# SRV-1_Expansion_Board.net
KiCad netlist of a schematic drawn in EAGLE
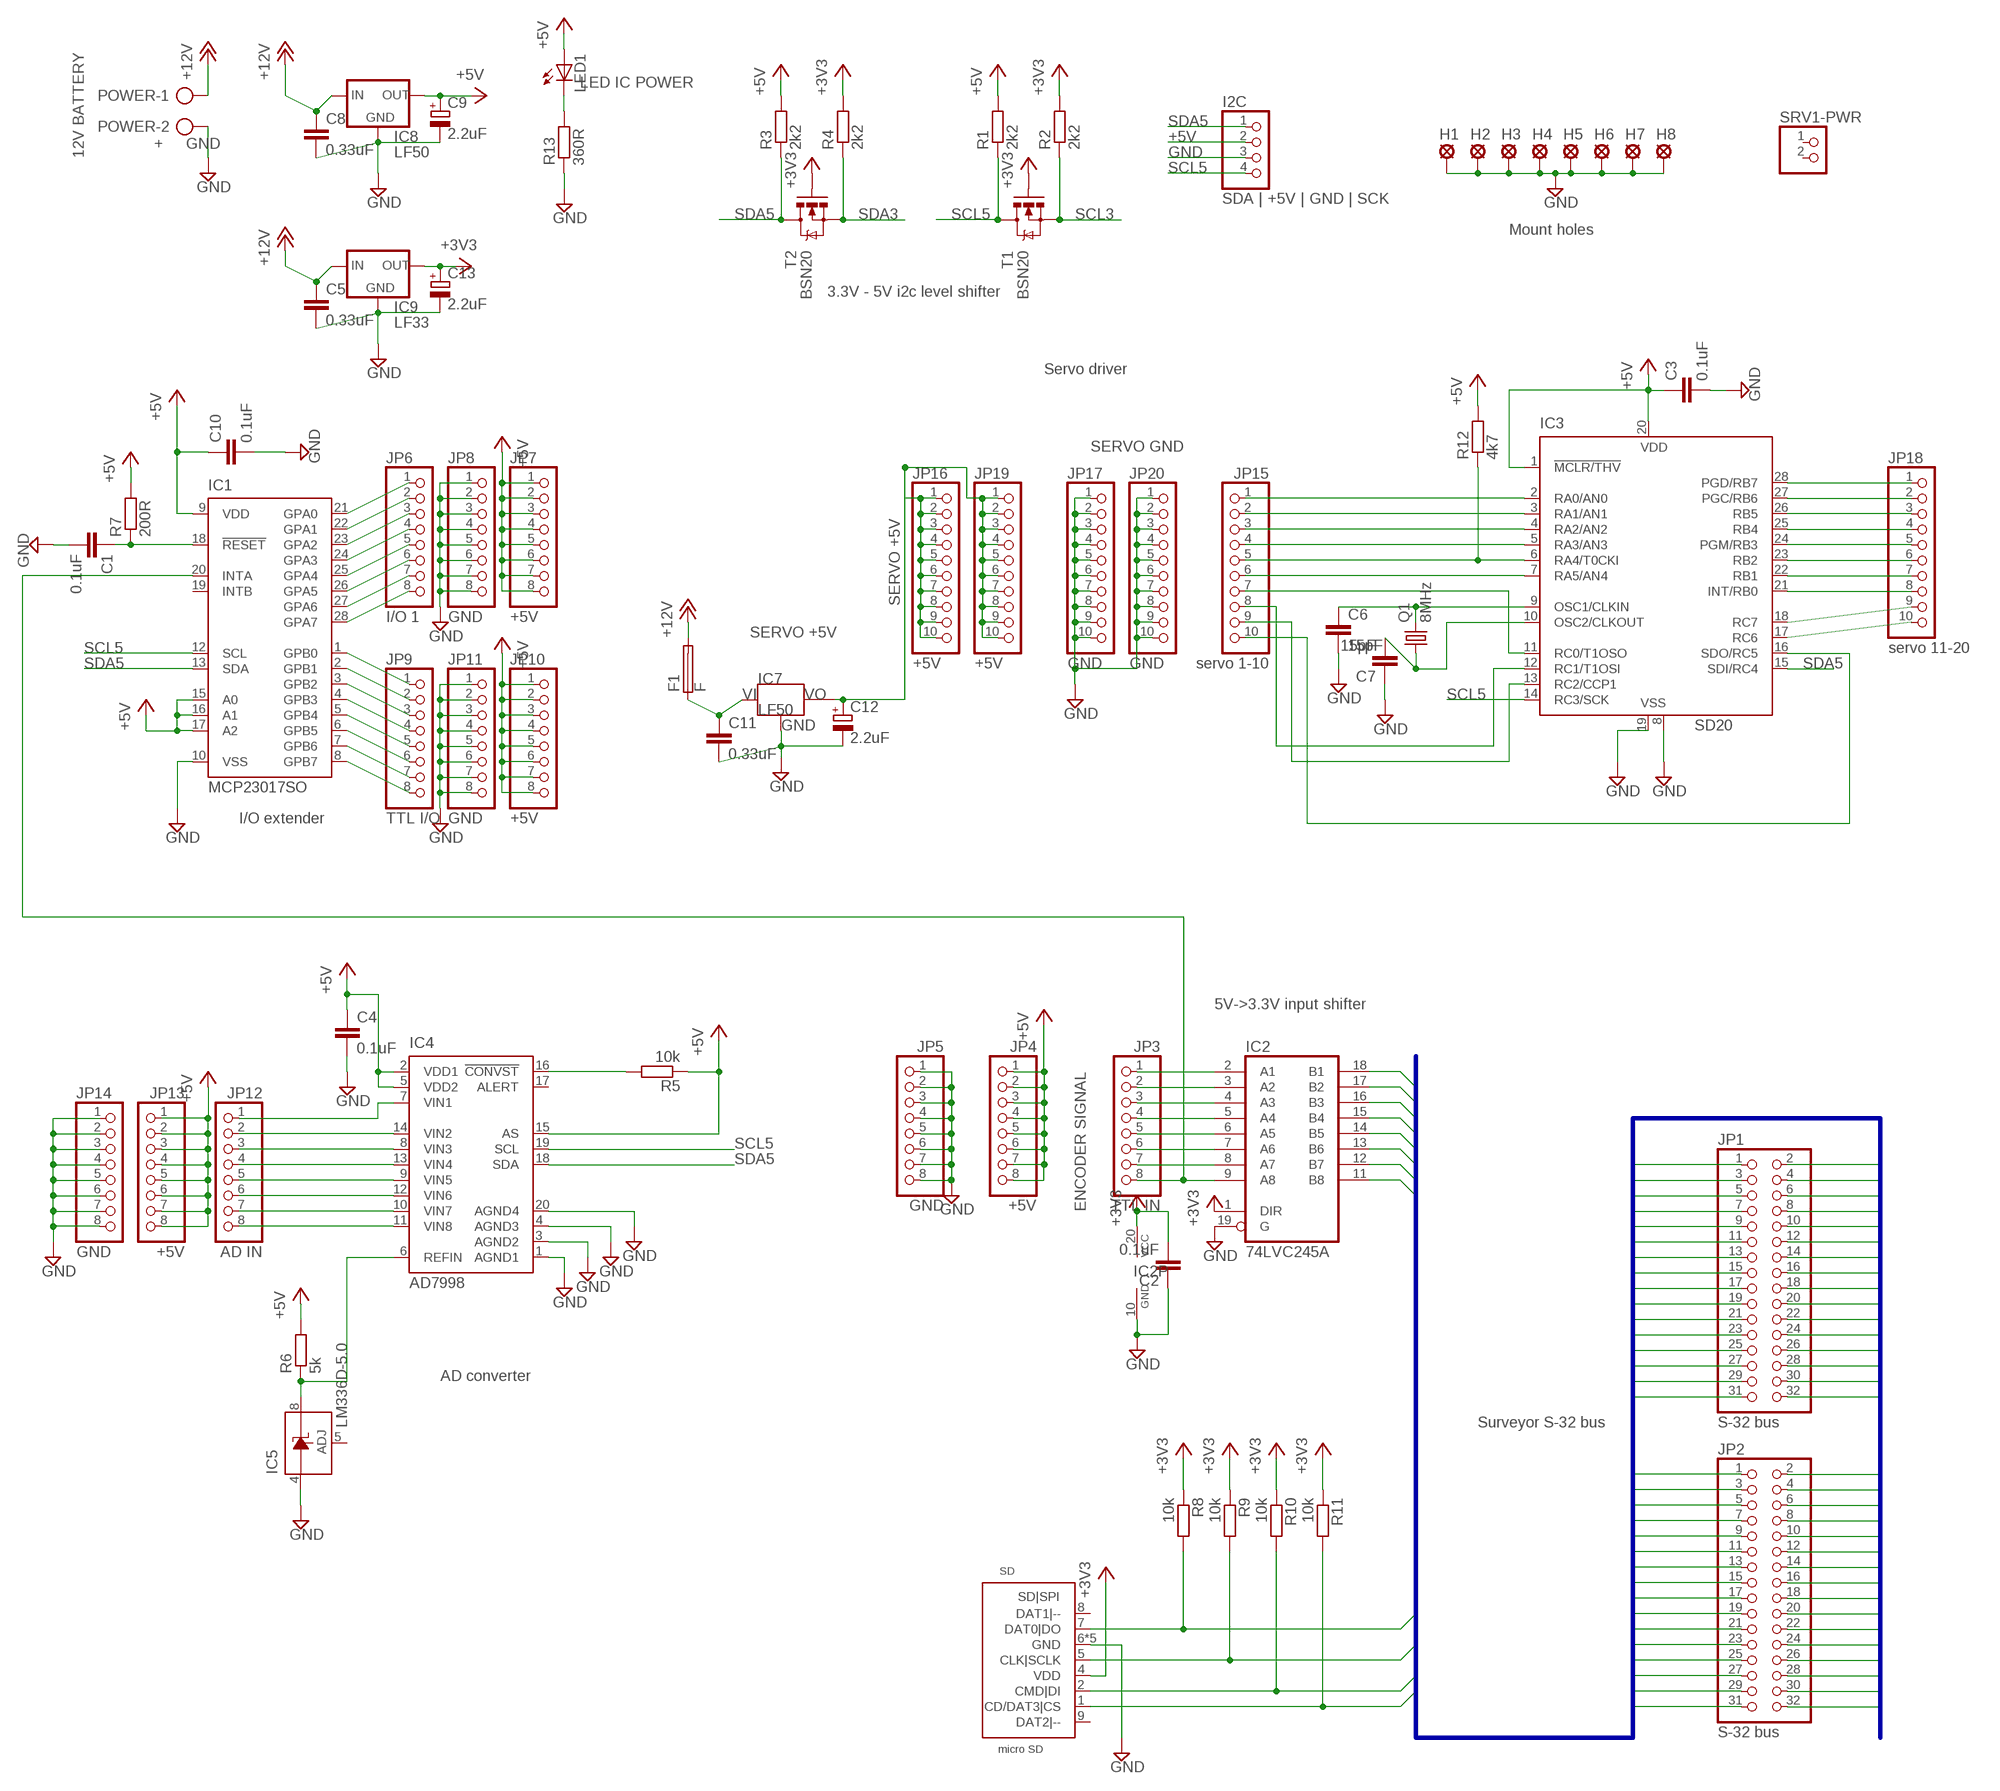
[diagram p0: schematic, sheet 1]

(export (version "E")
  (design (tool "Eeschema 10.0.6"))
  (components
    (comp (ref "C1")
      (value "0.1uF")
      (footprint "eagle-import:1206")
      (libsource (lib "eagle-import") (part "CAP1206"))
    )
    (comp (ref "C2")
      (value "0.1uF")
      (footprint "eagle-import:1206")
      (libsource (lib "eagle-import") (part "CAP1206"))
    )
    (comp (ref "C3")
      (value "0.1uF")
      (footprint "eagle-import:1206")
      (libsource (lib "eagle-import") (part "CAP1206"))
    )
    (comp (ref "C4")
      (value "0.1uF")
      (footprint "eagle-import:1206")
      (libsource (lib "eagle-import") (part "CAP1206"))
    )
    (comp (ref "C5")
      (value "0.33uF")
      (footprint "eagle-import:C025-024X044")
      (libsource (lib "eagle-import") (part "C-EU025-024X044"))
    )
    (comp (ref "C6")
      (value "15pF")
      (footprint "eagle-import:1206")
      (libsource (lib "eagle-import") (part "CAP1206"))
    )
    (comp (ref "C7")
      (value "15pF")
      (footprint "eagle-import:1206")
      (libsource (lib "eagle-import") (part "CAP1206"))
    )
    (comp (ref "C8")
      (value "0.33uF")
      (footprint "eagle-import:C025-024X044")
      (libsource (lib "eagle-import") (part "C-EU025-024X044"))
    )
    (comp (ref "C9")
      (value "2.2uF")
      (footprint "eagle-import:E1,8-4")
      (libsource (lib "eagle-import") (part "CPOL-EUE1.8-4"))
    )
    (comp (ref "C10")
      (value "0.1uF")
      (footprint "eagle-import:1206")
      (libsource (lib "eagle-import") (part "CAP1206"))
    )
    (comp (ref "C11")
      (value "0.33uF")
      (footprint "eagle-import:C025-024X044")
      (libsource (lib "eagle-import") (part "C-EU025-024X044"))
    )
    (comp (ref "C12")
      (value "2.2uF")
      (footprint "eagle-import:E1,8-4")
      (libsource (lib "eagle-import") (part "CPOL-EUE1.8-4"))
    )
    (comp (ref "C13")
      (value "2.2uF")
      (footprint "eagle-import:E1,8-4")
      (libsource (lib "eagle-import") (part "CPOL-EUE1.8-4"))
    )
    (comp (ref "F1") (value "F") (footprint "eagle-import:TE5") (libsource (lib "eagle-import") (part "TE5")))
    (comp (ref "H1")
      (value "LSP35")
      (footprint "eagle-import:LSP35")
      (libsource (lib "eagle-import") (part "LSP35"))
    )
    (comp (ref "H2")
      (value "LSP35")
      (footprint "eagle-import:LSP35")
      (libsource (lib "eagle-import") (part "LSP35"))
    )
    (comp (ref "H3")
      (value "LSP35")
      (footprint "eagle-import:LSP35")
      (libsource (lib "eagle-import") (part "LSP35"))
    )
    (comp (ref "H4")
      (value "LSP35")
      (footprint "eagle-import:LSP35")
      (libsource (lib "eagle-import") (part "LSP35"))
    )
    (comp (ref "H5")
      (value "LSP40")
      (footprint "eagle-import:LSP40")
      (libsource (lib "eagle-import") (part "LSP40"))
    )
    (comp (ref "H6")
      (value "LSP40")
      (footprint "eagle-import:LSP40")
      (libsource (lib "eagle-import") (part "LSP40"))
    )
    (comp (ref "H7")
      (value "LSP40")
      (footprint "eagle-import:LSP40")
      (libsource (lib "eagle-import") (part "LSP40"))
    )
    (comp (ref "H8")
      (value "LSP40")
      (footprint "eagle-import:LSP40")
      (libsource (lib "eagle-import") (part "LSP40"))
    )
    (comp (ref "I2C")
      (value "SDA | +5V | GND | SCK")
      (footprint "eagle-import:1X04")
      (libsource (lib "eagle-import") (part "PINHD-1X4"))
    )
    (comp (ref "IC1")
      (value "MCP23017SO")
      (footprint "eagle-import:SO28W")
      (fields (field (name "MF") "MICROCHIP") (field (name "MPN") "MCP23017-E/SO"))
      (libsource (lib "eagle-import") (part "MCP23017SO"))
    )
    (comp (ref "IC2")
      (value "74LVC245A")
      (footprint "eagle-import:SO20W")
      (libsource (lib "eagle-import") (part "74245DWLS"))
    )
    (comp (ref "IC3")
      (value "SD20")
      (footprint "eagle-import:DIL28-3")
      (fields (field (name "MF") "MICROCHIP") (field (name "MPN") "PIC16F872-I/SP"))
      (libsource (lib "eagle-import") (part "PIC16872PF"))
    )
    (comp (ref "IC4")
      (value "AD7998")
      (footprint "eagle-import:TSSOP20")
      (libsource (lib "eagle-import") (part "AD7998"))
    )
    (comp (ref "IC5")
      (value "LM336D-5.0")
      (footprint "eagle-import:SO08")
      (libsource (lib "eagle-import") (part "LM336D"))
    )
    (comp (ref "IC7")
      (value "LF50")
      (footprint "eagle-import:TO220V")
      (libsource (lib "eagle-import") (part "L7805"))
    )
    (comp (ref "IC8")
      (value "LF50")
      (footprint "eagle-import:DPAK")
      (libsource (lib "eagle-import") (part "78XXCDT"))
    )
    (comp (ref "IC9")
      (value "LF33")
      (footprint "eagle-import:DPAK")
      (libsource (lib "eagle-import") (part "78XXCDT"))
    )
    (comp (ref "JP1")
      (value "S-32 bus")
      (footprint "eagle-import:2X16")
      (libsource (lib "eagle-import") (part "PINHD-2X16"))
    )
    (comp (ref "JP2")
      (value "S-32 bus")
      (footprint "eagle-import:2X16")
      (libsource (lib "eagle-import") (part "PINHD-2X16"))
    )
    (comp (ref "JP3")
      (value "TTL IN")
      (footprint "eagle-import:1X08")
      (libsource (lib "eagle-import") (part "PINHD-1X8"))
    )
    (comp (ref "JP4")
      (value "+5V")
      (footprint "eagle-import:1X08")
      (libsource (lib "eagle-import") (part "PINHD-1X8"))
    )
    (comp (ref "JP5")
      (value "GND")
      (footprint "eagle-import:1X08")
      (libsource (lib "eagle-import") (part "PINHD-1X8"))
    )
    (comp (ref "JP6")
      (value "I/O 1")
      (footprint "eagle-import:1X08")
      (libsource (lib "eagle-import") (part "PINHD-1X8"))
    )
    (comp (ref "JP7")
      (value "+5V")
      (footprint "eagle-import:1X08")
      (libsource (lib "eagle-import") (part "PINHD-1X8"))
    )
    (comp (ref "JP8")
      (value "GND")
      (footprint "eagle-import:1X08")
      (libsource (lib "eagle-import") (part "PINHD-1X8"))
    )
    (comp (ref "JP9")
      (value "TTL I/O")
      (footprint "eagle-import:1X08")
      (libsource (lib "eagle-import") (part "PINHD-1X8"))
    )
    (comp (ref "JP10")
      (value "+5V")
      (footprint "eagle-import:1X08")
      (libsource (lib "eagle-import") (part "PINHD-1X8"))
    )
    (comp (ref "JP11")
      (value "GND")
      (footprint "eagle-import:1X08")
      (libsource (lib "eagle-import") (part "PINHD-1X8"))
    )
    (comp (ref "JP12")
      (value "AD IN")
      (footprint "eagle-import:1X08")
      (libsource (lib "eagle-import") (part "PINHD-1X8"))
    )
    (comp (ref "JP13")
      (value "+5V")
      (footprint "eagle-import:1X08")
      (libsource (lib "eagle-import") (part "PINHD-1X8"))
    )
    (comp (ref "JP14")
      (value "GND")
      (footprint "eagle-import:1X08")
      (libsource (lib "eagle-import") (part "PINHD-1X8"))
    )
    (comp (ref "JP15")
      (value "servo 1-10")
      (footprint "eagle-import:1X10")
      (libsource (lib "eagle-import") (part "PINHD-1X10"))
    )
    (comp (ref "JP16")
      (value "+5V")
      (footprint "eagle-import:1X10")
      (libsource (lib "eagle-import") (part "PINHD-1X10"))
    )
    (comp (ref "JP17")
      (value "GND")
      (footprint "eagle-import:1X10")
      (libsource (lib "eagle-import") (part "PINHD-1X10"))
    )
    (comp (ref "JP18")
      (value "servo 11-20")
      (footprint "eagle-import:1X10")
      (libsource (lib "eagle-import") (part "PINHD-1X10"))
    )
    (comp (ref "JP19")
      (value "+5V")
      (footprint "eagle-import:1X10")
      (libsource (lib "eagle-import") (part "PINHD-1X10"))
    )
    (comp (ref "JP20")
      (value "GND")
      (footprint "eagle-import:1X10")
      (libsource (lib "eagle-import") (part "PINHD-1X10"))
    )
    (comp (ref "LED1")
      (value "LEDCHIPLED_1206")
      (footprint "eagle-import:CHIPLED_1206")
      (libsource (lib "eagle-import") (part "LEDCHIPLED_1206"))
    )
    (comp (ref "POWER")
      (value "+ GND")
      (footprint "eagle-import:AK500_2")
      (libsource (lib "eagle-import") (part "AK500/2"))
    )
    (comp (ref "Q1")
      (value "8MHz")
      (footprint "eagle-import:HC49U70")
      (libsource (lib "eagle-import") (part "CRYSTALHC49U70"))
    )
    (comp (ref "R1")
      (value "2k2")
      (footprint "eagle-import:R1206")
      (libsource (lib "eagle-import") (part "R-EU_R1206"))
    )
    (comp (ref "R2")
      (value "2k2")
      (footprint "eagle-import:R1206")
      (libsource (lib "eagle-import") (part "R-EU_R1206"))
    )
    (comp (ref "R3")
      (value "2k2")
      (footprint "eagle-import:R1206")
      (libsource (lib "eagle-import") (part "R-EU_R1206"))
    )
    (comp (ref "R4")
      (value "2k2")
      (footprint "eagle-import:R1206")
      (libsource (lib "eagle-import") (part "R-EU_R1206"))
    )
    (comp (ref "R5")
      (value "10k")
      (footprint "eagle-import:R1206")
      (libsource (lib "eagle-import") (part "R-EU_R1206"))
    )
    (comp (ref "R6")
      (value "5k")
      (footprint "eagle-import:R1206")
      (libsource (lib "eagle-import") (part "R-EU_R1206"))
    )
    (comp (ref "R7")
      (value "200R")
      (footprint "eagle-import:R1206")
      (libsource (lib "eagle-import") (part "R-EU_R1206"))
    )
    (comp (ref "R8")
      (value "10k")
      (footprint "eagle-import:R1206")
      (libsource (lib "eagle-import") (part "R-EU_R1206"))
    )
    (comp (ref "R9")
      (value "10k")
      (footprint "eagle-import:R1206")
      (libsource (lib "eagle-import") (part "R-EU_R1206"))
    )
    (comp (ref "R10")
      (value "10k")
      (footprint "eagle-import:R1206")
      (libsource (lib "eagle-import") (part "R-EU_R1206"))
    )
    (comp (ref "R11")
      (value "10k")
      (footprint "eagle-import:R1206")
      (libsource (lib "eagle-import") (part "R-EU_R1206"))
    )
    (comp (ref "R12")
      (value "4k7")
      (footprint "eagle-import:R1206")
      (libsource (lib "eagle-import") (part "R-EU_R1206"))
    )
    (comp (ref "R13")
      (value "360R")
      (footprint "eagle-import:R1206")
      (libsource (lib "eagle-import") (part "R-EU_R1206"))
    )
    (comp (ref "SD")
      (value "micro SD")
      (footprint "eagle-import:SD-500901-0801")
      (libsource (lib "eagle-import") (part "MICRO-SD_CARD_SOCKET"))
    )
    (comp (ref "SRV1-PWR")
      (value "PINHD-1X2")
      (footprint "eagle-import:1X02")
      (libsource (lib "eagle-import") (part "PINHD-1X2"))
    )
    (comp (ref "T1")
      (value "BSN20")
      (footprint "eagle-import:SOT23")
      (libsource (lib "eagle-import") (part "BSN20"))
    )
    (comp (ref "T2")
      (value "BSN20")
      (footprint "eagle-import:SOT23")
      (libsource (lib "eagle-import") (part "BSN20"))
    )
  )
  (nets
    (net (code "1") (name "+3V3") (class "Default")
      (node (ref "C13") (pin "+") (pinfunction "+_+") (pintype "passive"))
      (node (ref "C2") (pin "2") (pinfunction "2_2") (pintype "passive"))
      (node (ref "IC2") (pin "1") (pinfunction "DIR_1") (pintype "input"))
      (node (ref "IC2") (pin "20") (pinfunction "VCC_20") (pintype "power_in"))
      (node (ref "IC9") (pin "3") (pinfunction "OUT_3") (pintype "passive"))
      (node (ref "JP1") (pin "1") (pinfunction "1_1") (pintype "passive"))
      (node (ref "JP2") (pin "1") (pinfunction "1_1") (pintype "passive"))
      (node (ref "R10") (pin "1") (pinfunction "1_1") (pintype "passive"))
      (node (ref "R11") (pin "1") (pinfunction "1_1") (pintype "passive"))
      (node (ref "R2") (pin "2") (pinfunction "2_2") (pintype "passive"))
      (node (ref "R4") (pin "2") (pinfunction "2_2") (pintype "passive"))
      (node (ref "R8") (pin "1") (pinfunction "1_1") (pintype "passive"))
      (node (ref "R9") (pin "1") (pinfunction "1_1") (pintype "passive"))
      (node (ref "SD") (pin "4") (pinfunction "VDD_4") (pintype "power_in"))
      (node (ref "T1") (pin "1") (pinfunction "G_1") (pintype "passive"))
      (node (ref "T2") (pin "1") (pinfunction "G_1") (pintype "passive"))
    )
    (net (code "2") (name "+5V") (class "Default")
      (node (ref "C10") (pin "1") (pinfunction "1_1") (pintype "passive"))
      (node (ref "C3") (pin "1") (pinfunction "1_1") (pintype "passive"))
      (node (ref "C4") (pin "1") (pinfunction "1_1") (pintype "passive"))
      (node (ref "C9") (pin "+") (pinfunction "+_+") (pintype "passive"))
      (node (ref "I2C") (pin "2") (pinfunction "2_2") (pintype "passive"))
      (node (ref "IC1") (pin "15") (pinfunction "A0_15") (pintype "input"))
      (node (ref "IC1") (pin "16") (pinfunction "A1_16") (pintype "input"))
      (node (ref "IC1") (pin "17") (pinfunction "A2_17") (pintype "input"))
      (node (ref "IC1") (pin "9") (pinfunction "VDD_9") (pintype "power_in"))
      (node (ref "IC3") (pin "1") (pinfunction "~{MCLR/THV}_1") (pintype "input"))
      (node (ref "IC3") (pin "20") (pinfunction "VDD_20") (pintype "power_in"))
      (node (ref "IC4") (pin "15") (pinfunction "AS_15") (pintype "input"))
      (node (ref "IC4") (pin "2") (pinfunction "VDD1_2") (pintype "power_in"))
      (node (ref "IC4") (pin "5") (pinfunction "VDD2_5") (pintype "power_in"))
      (node (ref "IC8") (pin "3") (pinfunction "OUT_3") (pintype "passive"))
      (node (ref "JP10") (pin "1") (pinfunction "1_1") (pintype "passive"))
      (node (ref "JP10") (pin "2") (pinfunction "2_2") (pintype "passive"))
      (node (ref "JP10") (pin "3") (pinfunction "3_3") (pintype "passive"))
      (node (ref "JP10") (pin "4") (pinfunction "4_4") (pintype "passive"))
      (node (ref "JP10") (pin "5") (pinfunction "5_5") (pintype "passive"))
      (node (ref "JP10") (pin "6") (pinfunction "6_6") (pintype "passive"))
      (node (ref "JP10") (pin "7") (pinfunction "7_7") (pintype "passive"))
      (node (ref "JP10") (pin "8") (pinfunction "8_8") (pintype "passive"))
      (node (ref "JP13") (pin "1") (pinfunction "1_1") (pintype "passive"))
      (node (ref "JP13") (pin "2") (pinfunction "2_2") (pintype "passive"))
      (node (ref "JP13") (pin "3") (pinfunction "3_3") (pintype "passive"))
      (node (ref "JP13") (pin "4") (pinfunction "4_4") (pintype "passive"))
      (node (ref "JP13") (pin "5") (pinfunction "5_5") (pintype "passive"))
      (node (ref "JP13") (pin "6") (pinfunction "6_6") (pintype "passive"))
      (node (ref "JP13") (pin "7") (pinfunction "7_7") (pintype "passive"))
      (node (ref "JP13") (pin "8") (pinfunction "8_8") (pintype "passive"))
      (node (ref "JP4") (pin "1") (pinfunction "1_1") (pintype "passive"))
      (node (ref "JP4") (pin "2") (pinfunction "2_2") (pintype "passive"))
      (node (ref "JP4") (pin "3") (pinfunction "3_3") (pintype "passive"))
      (node (ref "JP4") (pin "4") (pinfunction "4_4") (pintype "passive"))
      (node (ref "JP4") (pin "5") (pinfunction "5_5") (pintype "passive"))
      (node (ref "JP4") (pin "6") (pinfunction "6_6") (pintype "passive"))
      (node (ref "JP4") (pin "7") (pinfunction "7_7") (pintype "passive"))
      (node (ref "JP4") (pin "8") (pinfunction "8_8") (pintype "passive"))
      (node (ref "JP7") (pin "1") (pinfunction "1_1") (pintype "passive"))
      (node (ref "JP7") (pin "2") (pinfunction "2_2") (pintype "passive"))
      (node (ref "JP7") (pin "3") (pinfunction "3_3") (pintype "passive"))
      (node (ref "JP7") (pin "4") (pinfunction "4_4") (pintype "passive"))
      (node (ref "JP7") (pin "5") (pinfunction "5_5") (pintype "passive"))
      (node (ref "JP7") (pin "6") (pinfunction "6_6") (pintype "passive"))
      (node (ref "JP7") (pin "7") (pinfunction "7_7") (pintype "passive"))
      (node (ref "JP7") (pin "8") (pinfunction "8_8") (pintype "passive"))
      (node (ref "LED1") (pin "A") (pinfunction "A_A") (pintype "passive"))
      (node (ref "R1") (pin "2") (pinfunction "2_2") (pintype "passive"))
      (node (ref "R12") (pin "2") (pinfunction "2_2") (pintype "passive"))
      (node (ref "R3") (pin "2") (pinfunction "2_2") (pintype "passive"))
      (node (ref "R5") (pin "1") (pinfunction "1_1") (pintype "passive"))
      (node (ref "R6") (pin "2") (pinfunction "2_2") (pintype "passive"))
      (node (ref "R7") (pin "2") (pinfunction "2_2") (pintype "passive"))
    )
    (net (code "3") (name "+12V") (class "Default")
      (node (ref "C5") (pin "1") (pinfunction "1_1") (pintype "passive"))
      (node (ref "C8") (pin "1") (pinfunction "1_1") (pintype "passive"))
      (node (ref "F1") (pin "2") (pinfunction "2_2") (pintype "passive"))
      (node (ref "IC8") (pin "1") (pinfunction "IN_1") (pintype "input"))
      (node (ref "IC9") (pin "1") (pinfunction "IN_1") (pintype "input"))
      (node (ref "POWER") (pin "1") (pinfunction "KL_1") (pintype "passive"))
    )
    (net (code "4") (name "/S-32-BUS3") (class "Default")
      (node (ref "JP1") (pin "3") (pinfunction "3_3") (pintype "passive"))
      (node (ref "JP2") (pin "3") (pinfunction "3_3") (pintype "passive"))
    )
    (net (code "5") (name "/S-32-BUS4") (class "Default")
      (node (ref "JP1") (pin "4") (pinfunction "4_4") (pintype "passive"))
      (node (ref "JP2") (pin "4") (pinfunction "4_4") (pintype "passive"))
    )
    (net (code "6") (name "/S-32-BUS5") (class "Default")
      (node (ref "JP1") (pin "5") (pinfunction "5_5") (pintype "passive"))
      (node (ref "JP2") (pin "5") (pinfunction "5_5") (pintype "passive"))
    )
    (net (code "7") (name "/S-32-BUS6") (class "Default")
      (node (ref "JP1") (pin "6") (pinfunction "6_6") (pintype "passive"))
      (node (ref "JP2") (pin "6") (pinfunction "6_6") (pintype "passive"))
    )
    (net (code "8") (name "/S-32-BUS7") (class "Default")
      (node (ref "JP1") (pin "7") (pinfunction "7_7") (pintype "passive"))
      (node (ref "JP2") (pin "7") (pinfunction "7_7") (pintype "passive"))
    )
    (net (code "9") (name "/S-32-BUS8") (class "Default")
      (node (ref "JP1") (pin "8") (pinfunction "8_8") (pintype "passive"))
      (node (ref "JP2") (pin "8") (pinfunction "8_8") (pintype "passive"))
    )
    (net (code "10") (name "/S-32-BUS9") (class "Default")
      (node (ref "JP1") (pin "9") (pinfunction "9_9") (pintype "passive"))
      (node (ref "JP2") (pin "9") (pinfunction "9_9") (pintype "passive"))
      (node (ref "R10") (pin "2") (pinfunction "2_2") (pintype "passive"))
      (node (ref "SD") (pin "2") (pinfunction "CMD|DI_2") (pintype "bidirectional"))
    )
    (net (code "11") (name "/S-32-BUS10") (class "Default")
      (node (ref "JP1") (pin "10") (pinfunction "10_10") (pintype "passive"))
      (node (ref "JP2") (pin "10") (pinfunction "10_10") (pintype "passive"))
      (node (ref "R8") (pin "2") (pinfunction "2_2") (pintype "passive"))
      (node (ref "SD") (pin "7") (pinfunction "DAT0|DO_7") (pintype "bidirectional"))
    )
    (net (code "12") (name "/S-32-BUS11") (class "Default")
      (node (ref "JP1") (pin "11") (pinfunction "11_11") (pintype "passive"))
      (node (ref "JP2") (pin "11") (pinfunction "11_11") (pintype "passive"))
      (node (ref "R9") (pin "2") (pinfunction "2_2") (pintype "passive"))
      (node (ref "SD") (pin "5") (pinfunction "CLK|SCLK_5") (pintype "bidirectional"))
    )
    (net (code "13") (name "/S-32-BUS12") (class "Default")
      (node (ref "JP1") (pin "12") (pinfunction "12_12") (pintype "passive"))
      (node (ref "JP2") (pin "12") (pinfunction "12_12") (pintype "passive"))
      (node (ref "R11") (pin "2") (pinfunction "2_2") (pintype "passive"))
      (node (ref "SD") (pin "1") (pinfunction "CD/DAT3|CS_1") (pintype "bidirectional"))
    )
    (net (code "14") (name "/S-32-BUS13") (class "Default")
      (node (ref "JP1") (pin "13") (pinfunction "13_13") (pintype "passive"))
      (node (ref "JP2") (pin "13") (pinfunction "13_13") (pintype "passive"))
    )
    (net (code "15") (name "/S-32-BUS17") (class "Default")
      (node (ref "JP1") (pin "17") (pinfunction "17_17") (pintype "passive"))
      (node (ref "JP2") (pin "17") (pinfunction "17_17") (pintype "passive"))
    )
    (net (code "16") (name "/S-32-BUS18") (class "Default")
      (node (ref "JP1") (pin "18") (pinfunction "18_18") (pintype "passive"))
      (node (ref "JP2") (pin "18") (pinfunction "18_18") (pintype "passive"))
    )
    (net (code "17") (name "/S-32-BUS19") (class "Default")
      (node (ref "JP1") (pin "19") (pinfunction "19_19") (pintype "passive"))
      (node (ref "JP2") (pin "19") (pinfunction "19_19") (pintype "passive"))
    )
    (net (code "18") (name "/S-32-BUS20") (class "Default")
      (node (ref "JP1") (pin "20") (pinfunction "20_20") (pintype "passive"))
      (node (ref "JP2") (pin "20") (pinfunction "20_20") (pintype "passive"))
    )
    (net (code "19") (name "/S-32-BUS21") (class "Default")
      (node (ref "JP1") (pin "21") (pinfunction "21_21") (pintype "passive"))
      (node (ref "JP2") (pin "21") (pinfunction "21_21") (pintype "passive"))
    )
    (net (code "20") (name "/S-32-BUS22") (class "Default")
      (node (ref "JP1") (pin "22") (pinfunction "22_22") (pintype "passive"))
      (node (ref "JP2") (pin "22") (pinfunction "22_22") (pintype "passive"))
    )
    (net (code "21") (name "/S-32-BUS23") (class "Default")
      (node (ref "JP1") (pin "23") (pinfunction "23_23") (pintype "passive"))
      (node (ref "JP2") (pin "23") (pinfunction "23_23") (pintype "passive"))
    )
    (net (code "22") (name "/S-32-BUS24") (class "Default")
      (node (ref "JP1") (pin "24") (pinfunction "24_24") (pintype "passive"))
      (node (ref "JP2") (pin "24") (pinfunction "24_24") (pintype "passive"))
    )
    (net (code "23") (name "/S-32-BUS25") (class "Default")
      (node (ref "IC2") (pin "18") (pinfunction "B1_18") (pintype "bidirectional"))
      (node (ref "JP1") (pin "25") (pinfunction "25_25") (pintype "passive"))
      (node (ref "JP2") (pin "25") (pinfunction "25_25") (pintype "passive"))
    )
    (net (code "24") (name "/S-32-BUS26") (class "Default")
      (node (ref "IC2") (pin "17") (pinfunction "B2_17") (pintype "bidirectional"))
      (node (ref "JP1") (pin "26") (pinfunction "26_26") (pintype "passive"))
      (node (ref "JP2") (pin "26") (pinfunction "26_26") (pintype "passive"))
    )
    (net (code "25") (name "/S-32-BUS27") (class "Default")
      (node (ref "IC2") (pin "16") (pinfunction "B3_16") (pintype "bidirectional"))
      (node (ref "JP1") (pin "27") (pinfunction "27_27") (pintype "passive"))
      (node (ref "JP2") (pin "27") (pinfunction "27_27") (pintype "passive"))
    )
    (net (code "26") (name "/S-32-BUS28") (class "Default")
      (node (ref "IC2") (pin "15") (pinfunction "B4_15") (pintype "bidirectional"))
      (node (ref "JP1") (pin "28") (pinfunction "28_28") (pintype "passive"))
      (node (ref "JP2") (pin "28") (pinfunction "28_28") (pintype "passive"))
    )
    (net (code "27") (name "/S-32-BUS29") (class "Default")
      (node (ref "IC2") (pin "14") (pinfunction "B5_14") (pintype "bidirectional"))
      (node (ref "JP1") (pin "29") (pinfunction "29_29") (pintype "passive"))
      (node (ref "JP2") (pin "29") (pinfunction "29_29") (pintype "passive"))
    )
    (net (code "28") (name "/S-32-BUS30") (class "Default")
      (node (ref "IC2") (pin "13") (pinfunction "B6_13") (pintype "bidirectional"))
      (node (ref "JP1") (pin "30") (pinfunction "30_30") (pintype "passive"))
      (node (ref "JP2") (pin "30") (pinfunction "30_30") (pintype "passive"))
    )
    (net (code "29") (name "/S-32-BUS31") (class "Default")
      (node (ref "IC2") (pin "12") (pinfunction "B7_12") (pintype "bidirectional"))
      (node (ref "JP1") (pin "31") (pinfunction "31_31") (pintype "passive"))
      (node (ref "JP2") (pin "31") (pinfunction "31_31") (pintype "passive"))
    )
    (net (code "30") (name "/S-32-BUS32") (class "Default")
      (node (ref "IC2") (pin "11") (pinfunction "B8_11") (pintype "bidirectional"))
      (node (ref "JP1") (pin "32") (pinfunction "32_32") (pintype "passive"))
      (node (ref "JP2") (pin "32") (pinfunction "32_32") (pintype "passive"))
    )
    (net (code "31") (name "/SCL3") (class "Default")
      (node (ref "JP1") (pin "14") (pinfunction "14_14") (pintype "passive"))
      (node (ref "JP2") (pin "14") (pinfunction "14_14") (pintype "passive"))
      (node (ref "R2") (pin "1") (pinfunction "1_1") (pintype "passive"))
      (node (ref "T1") (pin "2") (pinfunction "S_2") (pintype "passive"))
    )
    (net (code "32") (name "/SCL5") (class "Default")
      (node (ref "I2C") (pin "4") (pinfunction "4_4") (pintype "passive"))
      (node (ref "IC1") (pin "12") (pinfunction "SCL_12") (pintype "input"))
      (node (ref "IC3") (pin "14") (pinfunction "RC3/SCK_14") (pintype "bidirectional"))
      (node (ref "IC4") (pin "19") (pinfunction "SCL_19") (pintype "input"))
      (node (ref "R1") (pin "1") (pinfunction "1_1") (pintype "passive"))
      (node (ref "T1") (pin "3") (pinfunction "D_3") (pintype "passive"))
    )
    (net (code "33") (name "/SDA3") (class "Default")
      (node (ref "JP1") (pin "15") (pinfunction "15_15") (pintype "passive"))
      (node (ref "JP2") (pin "15") (pinfunction "15_15") (pintype "passive"))
      (node (ref "R4") (pin "1") (pinfunction "1_1") (pintype "passive"))
      (node (ref "T2") (pin "2") (pinfunction "S_2") (pintype "passive"))
    )
    (net (code "34") (name "/SDA5") (class "Default")
      (node (ref "I2C") (pin "1") (pinfunction "1_1") (pintype "passive"))
      (node (ref "IC1") (pin "13") (pinfunction "SDA_13") (pintype "bidirectional"))
      (node (ref "IC3") (pin "15") (pinfunction "SDI/RC4_15") (pintype "bidirectional"))
      (node (ref "IC4") (pin "18") (pinfunction "SDA_18") (pintype "bidirectional"))
      (node (ref "R3") (pin "1") (pinfunction "1_1") (pintype "passive"))
      (node (ref "T2") (pin "3") (pinfunction "D_3") (pintype "passive"))
    )
    (net (code "35") (name "GND") (class "Default")
      (node (ref "C1") (pin "2") (pinfunction "2_2") (pintype "passive"))
      (node (ref "C10") (pin "2") (pinfunction "2_2") (pintype "passive"))
      (node (ref "C11") (pin "2") (pinfunction "2_2") (pintype "passive"))
      (node (ref "C12") (pin "-") (pinfunction "-_-") (pintype "passive"))
      (node (ref "C13") (pin "-") (pinfunction "-_-") (pintype "passive"))
      (node (ref "C2") (pin "1") (pinfunction "1_1") (pintype "passive"))
      (node (ref "C3") (pin "2") (pinfunction "2_2") (pintype "passive"))
      (node (ref "C4") (pin "2") (pinfunction "2_2") (pintype "passive"))
      (node (ref "C5") (pin "2") (pinfunction "2_2") (pintype "passive"))
      (node (ref "C6") (pin "2") (pinfunction "2_2") (pintype "passive"))
      (node (ref "C7") (pin "1") (pinfunction "1_1") (pintype "passive"))
      (node (ref "C8") (pin "2") (pinfunction "2_2") (pintype "passive"))
      (node (ref "C9") (pin "-") (pinfunction "-_-") (pintype "passive"))
      (node (ref "H1") (pin "MP") (pinfunction "MP_MP") (pintype "passive"))
      (node (ref "H2") (pin "MP") (pinfunction "MP_MP") (pintype "passive"))
      (node (ref "H3") (pin "MP") (pinfunction "MP_MP") (pintype "passive"))
      (node (ref "H4") (pin "MP") (pinfunction "MP_MP") (pintype "passive"))
      (node (ref "H5") (pin "MP") (pinfunction "MP_MP") (pintype "passive"))
      (node (ref "H6") (pin "MP") (pinfunction "MP_MP") (pintype "passive"))
      (node (ref "H7") (pin "MP") (pinfunction "MP_MP") (pintype "passive"))
      (node (ref "H8") (pin "MP") (pinfunction "MP_MP") (pintype "passive"))
      (node (ref "I2C") (pin "3") (pinfunction "3_3") (pintype "passive"))
      (node (ref "IC1") (pin "10") (pinfunction "VSS_10") (pintype "power_in"))
      (node (ref "IC2") (pin "10") (pinfunction "GND_10") (pintype "power_in"))
      (node (ref "IC2") (pin "19") (pinfunction "G_19") (pintype "input"))
      (node (ref "IC3") (pin "19") (pinfunction "VSS_19") (pintype "power_in"))
      (node (ref "IC3") (pin "8") (pinfunction "VSS_8") (pintype "power_in"))
      (node (ref "IC4") (pin "1") (pinfunction "AGND1_1") (pintype "power_in"))
      (node (ref "IC4") (pin "20") (pinfunction "AGND4_20") (pintype "power_in"))
      (node (ref "IC4") (pin "3") (pinfunction "AGND2_3") (pintype "power_in"))
      (node (ref "IC4") (pin "4") (pinfunction "AGND3_4") (pintype "power_in"))
      (node (ref "IC5") (pin "4") (pinfunction "A_4") (pintype "input"))
      (node (ref "IC7") (pin "3") (pinfunction "GND_3") (pintype "power_in"))
      (node (ref "IC8") (pin "2") (pinfunction "GND_2") (pintype "input"))
      (node (ref "IC9") (pin "2") (pinfunction "GND_2") (pintype "input"))
      (node (ref "JP1") (pin "16") (pinfunction "16_16") (pintype "passive"))
      (node (ref "JP1") (pin "2") (pinfunction "2_2") (pintype "passive"))
      (node (ref "JP11") (pin "1") (pinfunction "1_1") (pintype "passive"))
      (node (ref "JP11") (pin "2") (pinfunction "2_2") (pintype "passive"))
      (node (ref "JP11") (pin "3") (pinfunction "3_3") (pintype "passive"))
      (node (ref "JP11") (pin "4") (pinfunction "4_4") (pintype "passive"))
      (node (ref "JP11") (pin "5") (pinfunction "5_5") (pintype "passive"))
      (node (ref "JP11") (pin "6") (pinfunction "6_6") (pintype "passive"))
      (node (ref "JP11") (pin "7") (pinfunction "7_7") (pintype "passive"))
      (node (ref "JP11") (pin "8") (pinfunction "8_8") (pintype "passive"))
      (node (ref "JP14") (pin "1") (pinfunction "1_1") (pintype "passive"))
      (node (ref "JP14") (pin "2") (pinfunction "2_2") (pintype "passive"))
      (node (ref "JP14") (pin "3") (pinfunction "3_3") (pintype "passive"))
      (node (ref "JP14") (pin "4") (pinfunction "4_4") (pintype "passive"))
      (node (ref "JP14") (pin "5") (pinfunction "5_5") (pintype "passive"))
      (node (ref "JP14") (pin "6") (pinfunction "6_6") (pintype "passive"))
      (node (ref "JP14") (pin "7") (pinfunction "7_7") (pintype "passive"))
      (node (ref "JP14") (pin "8") (pinfunction "8_8") (pintype "passive"))
      (node (ref "JP17") (pin "1") (pinfunction "1_1") (pintype "passive"))
      (node (ref "JP17") (pin "10") (pinfunction "10_10") (pintype "passive"))
      (node (ref "JP17") (pin "2") (pinfunction "2_2") (pintype "passive"))
      (node (ref "JP17") (pin "3") (pinfunction "3_3") (pintype "passive"))
      (node (ref "JP17") (pin "4") (pinfunction "4_4") (pintype "passive"))
      (node (ref "JP17") (pin "5") (pinfunction "5_5") (pintype "passive"))
      (node (ref "JP17") (pin "6") (pinfunction "6_6") (pintype "passive"))
      (node (ref "JP17") (pin "7") (pinfunction "7_7") (pintype "passive"))
      (node (ref "JP17") (pin "8") (pinfunction "8_8") (pintype "passive"))
      (node (ref "JP17") (pin "9") (pinfunction "9_9") (pintype "passive"))
      (node (ref "JP2") (pin "16") (pinfunction "16_16") (pintype "passive"))
      (node (ref "JP2") (pin "2") (pinfunction "2_2") (pintype "passive"))
      (node (ref "JP20") (pin "1") (pinfunction "1_1") (pintype "passive"))
      (node (ref "JP20") (pin "10") (pinfunction "10_10") (pintype "passive"))
      (node (ref "JP20") (pin "2") (pinfunction "2_2") (pintype "passive"))
      (node (ref "JP20") (pin "3") (pinfunction "3_3") (pintype "passive"))
      (node (ref "JP20") (pin "4") (pinfunction "4_4") (pintype "passive"))
      (node (ref "JP20") (pin "5") (pinfunction "5_5") (pintype "passive"))
      (node (ref "JP20") (pin "6") (pinfunction "6_6") (pintype "passive"))
      (node (ref "JP20") (pin "7") (pinfunction "7_7") (pintype "passive"))
      (node (ref "JP20") (pin "8") (pinfunction "8_8") (pintype "passive"))
      (node (ref "JP20") (pin "9") (pinfunction "9_9") (pintype "passive"))
      (node (ref "JP5") (pin "1") (pinfunction "1_1") (pintype "passive"))
      (node (ref "JP5") (pin "2") (pinfunction "2_2") (pintype "passive"))
      (node (ref "JP5") (pin "3") (pinfunction "3_3") (pintype "passive"))
      (node (ref "JP5") (pin "4") (pinfunction "4_4") (pintype "passive"))
      (node (ref "JP5") (pin "5") (pinfunction "5_5") (pintype "passive"))
      (node (ref "JP5") (pin "6") (pinfunction "6_6") (pintype "passive"))
      (node (ref "JP5") (pin "7") (pinfunction "7_7") (pintype "passive"))
      (node (ref "JP5") (pin "8") (pinfunction "8_8") (pintype "passive"))
      (node (ref "JP8") (pin "1") (pinfunction "1_1") (pintype "passive"))
      (node (ref "JP8") (pin "2") (pinfunction "2_2") (pintype "passive"))
      (node (ref "JP8") (pin "3") (pinfunction "3_3") (pintype "passive"))
      (node (ref "JP8") (pin "4") (pinfunction "4_4") (pintype "passive"))
      (node (ref "JP8") (pin "5") (pinfunction "5_5") (pintype "passive"))
      (node (ref "JP8") (pin "6") (pinfunction "6_6") (pintype "passive"))
      (node (ref "JP8") (pin "7") (pinfunction "7_7") (pintype "passive"))
      (node (ref "JP8") (pin "8") (pinfunction "8_8") (pintype "passive"))
      (node (ref "POWER") (pin "2") (pinfunction "KL_2") (pintype "passive"))
      (node (ref "R13") (pin "1") (pinfunction "1_1") (pintype "passive"))
      (node (ref "SD") (pin "6") (pinfunction "GND_6") (pintype "power_in"))
      (node (ref "SD") (pin "GND1") (pinfunction "GND_GND1") (pintype "power_in"))
      (node (ref "SD") (pin "GND2") (pinfunction "GND_GND2") (pintype "power_in"))
      (node (ref "SD") (pin "GND3") (pinfunction "GND_GND3") (pintype "power_in"))
      (node (ref "SD") (pin "GND4") (pinfunction "GND_GND4") (pintype "power_in"))
    )
    (net (code "36") (name "Net-(IC1-GPA0)") (class "Default")
      (node (ref "IC1") (pin "21") (pinfunction "GPA0_21") (pintype "bidirectional"))
      (node (ref "JP6") (pin "1") (pinfunction "1_1") (pintype "passive"))
    )
    (net (code "37") (name "Net-(IC1-GPA1)") (class "Default")
      (node (ref "IC1") (pin "22") (pinfunction "GPA1_22") (pintype "bidirectional"))
      (node (ref "JP6") (pin "2") (pinfunction "2_2") (pintype "passive"))
    )
    (net (code "38") (name "Net-(IC1-GPA2)") (class "Default")
      (node (ref "IC1") (pin "23") (pinfunction "GPA2_23") (pintype "bidirectional"))
      (node (ref "JP6") (pin "3") (pinfunction "3_3") (pintype "passive"))
    )
    (net (code "39") (name "Net-(IC1-GPA3)") (class "Default")
      (node (ref "IC1") (pin "24") (pinfunction "GPA3_24") (pintype "bidirectional"))
      (node (ref "JP6") (pin "4") (pinfunction "4_4") (pintype "passive"))
    )
    (net (code "40") (name "Net-(IC1-GPA4)") (class "Default")
      (node (ref "IC1") (pin "25") (pinfunction "GPA4_25") (pintype "bidirectional"))
      (node (ref "JP6") (pin "5") (pinfunction "5_5") (pintype "passive"))
    )
    (net (code "41") (name "Net-(IC1-GPA5)") (class "Default")
      (node (ref "IC1") (pin "26") (pinfunction "GPA5_26") (pintype "bidirectional"))
      (node (ref "JP6") (pin "6") (pinfunction "6_6") (pintype "passive"))
    )
    (net (code "42") (name "Net-(IC1-GPA6)") (class "Default")
      (node (ref "IC1") (pin "27") (pinfunction "GPA6_27") (pintype "bidirectional"))
      (node (ref "JP6") (pin "7") (pinfunction "7_7") (pintype "passive"))
    )
    (net (code "43") (name "Net-(IC1-GPA7)") (class "Default")
      (node (ref "IC1") (pin "28") (pinfunction "GPA7_28") (pintype "bidirectional"))
      (node (ref "JP6") (pin "8") (pinfunction "8_8") (pintype "passive"))
    )
    (net (code "44") (name "Net-(IC1-GPB0)") (class "Default")
      (node (ref "IC1") (pin "1") (pinfunction "GPB0_1") (pintype "bidirectional"))
      (node (ref "JP9") (pin "1") (pinfunction "1_1") (pintype "passive"))
    )
    (net (code "45") (name "Net-(IC1-GPB1)") (class "Default")
      (node (ref "IC1") (pin "2") (pinfunction "GPB1_2") (pintype "bidirectional"))
      (node (ref "JP9") (pin "2") (pinfunction "2_2") (pintype "passive"))
    )
    (net (code "46") (name "Net-(IC1-GPB2)") (class "Default")
      (node (ref "IC1") (pin "3") (pinfunction "GPB2_3") (pintype "bidirectional"))
      (node (ref "JP9") (pin "3") (pinfunction "3_3") (pintype "passive"))
    )
    (net (code "47") (name "Net-(IC1-GPB3)") (class "Default")
      (node (ref "IC1") (pin "4") (pinfunction "GPB3_4") (pintype "bidirectional"))
      (node (ref "JP9") (pin "4") (pinfunction "4_4") (pintype "passive"))
    )
    (net (code "48") (name "Net-(IC1-GPB4)") (class "Default")
      (node (ref "IC1") (pin "5") (pinfunction "GPB4_5") (pintype "bidirectional"))
      (node (ref "JP9") (pin "5") (pinfunction "5_5") (pintype "passive"))
    )
    (net (code "49") (name "Net-(IC1-GPB5)") (class "Default")
      (node (ref "IC1") (pin "6") (pinfunction "GPB5_6") (pintype "bidirectional"))
      (node (ref "JP9") (pin "6") (pinfunction "6_6") (pintype "passive"))
    )
    (net (code "50") (name "Net-(IC1-GPB6)") (class "Default")
      (node (ref "IC1") (pin "7") (pinfunction "GPB6_7") (pintype "bidirectional"))
      (node (ref "JP9") (pin "7") (pinfunction "7_7") (pintype "passive"))
    )
    (net (code "51") (name "Net-(IC1-GPB7)") (class "Default")
      (node (ref "IC1") (pin "8") (pinfunction "GPB7_8") (pintype "bidirectional"))
      (node (ref "JP9") (pin "8") (pinfunction "8_8") (pintype "passive"))
    )
    (net (code "52") (name "Net-(IC1-INTA)") (class "Default")
      (node (ref "IC1") (pin "20") (pinfunction "INTA_20") (pintype "output"))
      (node (ref "IC2") (pin "9") (pinfunction "A8_9") (pintype "bidirectional"))
      (node (ref "JP3") (pin "8") (pinfunction "8_8") (pintype "passive"))
    )
    (net (code "53") (name "Net-(IC1-~{RESET})") (class "Default")
      (node (ref "C1") (pin "1") (pinfunction "1_1") (pintype "passive"))
      (node (ref "IC1") (pin "18") (pinfunction "~{RESET}_18") (pintype "input"))
      (node (ref "R7") (pin "1") (pinfunction "1_1") (pintype "passive"))
    )
    (net (code "54") (name "Net-(IC2A-A1)") (class "Default")
      (node (ref "IC2") (pin "2") (pinfunction "A1_2") (pintype "bidirectional"))
      (node (ref "JP3") (pin "1") (pinfunction "1_1") (pintype "passive"))
    )
    (net (code "55") (name "Net-(IC2A-A2)") (class "Default")
      (node (ref "IC2") (pin "3") (pinfunction "A2_3") (pintype "bidirectional"))
      (node (ref "JP3") (pin "2") (pinfunction "2_2") (pintype "passive"))
    )
    (net (code "56") (name "Net-(IC2A-A3)") (class "Default")
      (node (ref "IC2") (pin "4") (pinfunction "A3_4") (pintype "bidirectional"))
      (node (ref "JP3") (pin "3") (pinfunction "3_3") (pintype "passive"))
    )
    (net (code "57") (name "Net-(IC2A-A4)") (class "Default")
      (node (ref "IC2") (pin "5") (pinfunction "A4_5") (pintype "bidirectional"))
      (node (ref "JP3") (pin "4") (pinfunction "4_4") (pintype "passive"))
    )
    (net (code "58") (name "Net-(IC2A-A5)") (class "Default")
      (node (ref "IC2") (pin "6") (pinfunction "A5_6") (pintype "bidirectional"))
      (node (ref "JP3") (pin "5") (pinfunction "5_5") (pintype "passive"))
    )
    (net (code "59") (name "Net-(IC2A-A6)") (class "Default")
      (node (ref "IC2") (pin "7") (pinfunction "A6_7") (pintype "bidirectional"))
      (node (ref "JP3") (pin "6") (pinfunction "6_6") (pintype "passive"))
    )
    (net (code "60") (name "Net-(IC2A-A7)") (class "Default")
      (node (ref "IC2") (pin "8") (pinfunction "A7_8") (pintype "bidirectional"))
      (node (ref "JP3") (pin "7") (pinfunction "7_7") (pintype "passive"))
    )
    (net (code "61") (name "Net-(IC3-INT{slash}RB0)") (class "Default")
      (node (ref "IC3") (pin "21") (pinfunction "INT/RB0_21") (pintype "bidirectional"))
      (node (ref "JP18") (pin "8") (pinfunction "8_8") (pintype "passive"))
    )
    (net (code "62") (name "Net-(IC3-OSC1{slash}CLKIN)") (class "Default")
      (node (ref "C6") (pin "1") (pinfunction "1_1") (pintype "passive"))
      (node (ref "IC3") (pin "9") (pinfunction "OSC1/CLKIN_9") (pintype "input"))
      (node (ref "Q1") (pin "2") (pinfunction "2_2") (pintype "passive"))
    )
    (net (code "63") (name "Net-(IC3-OSC2{slash}CLKOUT)") (class "Default")
      (node (ref "C7") (pin "2") (pinfunction "2_2") (pintype "passive"))
      (node (ref "IC3") (pin "10") (pinfunction "OSC2/CLKOUT_10") (pintype "output"))
      (node (ref "Q1") (pin "1") (pinfunction "1_1") (pintype "passive"))
    )
    (net (code "64") (name "Net-(IC3-PGC{slash}RB6)") (class "Default")
      (node (ref "IC3") (pin "27") (pinfunction "PGC/RB6_27") (pintype "bidirectional"))
      (node (ref "JP18") (pin "2") (pinfunction "2_2") (pintype "passive"))
    )
    (net (code "65") (name "Net-(IC3-PGD{slash}RB7)") (class "Default")
      (node (ref "IC3") (pin "28") (pinfunction "PGD/RB7_28") (pintype "bidirectional"))
      (node (ref "JP18") (pin "1") (pinfunction "1_1") (pintype "passive"))
    )
    (net (code "66") (name "Net-(IC3-PGM{slash}RB3)") (class "Default")
      (node (ref "IC3") (pin "24") (pinfunction "PGM/RB3_24") (pintype "bidirectional"))
      (node (ref "JP18") (pin "5") (pinfunction "5_5") (pintype "passive"))
    )
    (net (code "67") (name "Net-(IC3-RA0{slash}AN0)") (class "Default")
      (node (ref "IC3") (pin "2") (pinfunction "RA0/AN0_2") (pintype "bidirectional"))
      (node (ref "JP15") (pin "1") (pinfunction "1_1") (pintype "passive"))
    )
    (net (code "68") (name "Net-(IC3-RA1{slash}AN1)") (class "Default")
      (node (ref "IC3") (pin "3") (pinfunction "RA1/AN1_3") (pintype "bidirectional"))
      (node (ref "JP15") (pin "2") (pinfunction "2_2") (pintype "passive"))
    )
    (net (code "69") (name "Net-(IC3-RA2{slash}AN2)") (class "Default")
      (node (ref "IC3") (pin "4") (pinfunction "RA2/AN2_4") (pintype "bidirectional"))
      (node (ref "JP15") (pin "3") (pinfunction "3_3") (pintype "passive"))
    )
    (net (code "70") (name "Net-(IC3-RA3{slash}AN3)") (class "Default")
      (node (ref "IC3") (pin "5") (pinfunction "RA3/AN3_5") (pintype "bidirectional"))
      (node (ref "JP15") (pin "4") (pinfunction "4_4") (pintype "passive"))
    )
    (net (code "71") (name "Net-(IC3-RA4{slash}T0CKI)") (class "Default")
      (node (ref "IC3") (pin "6") (pinfunction "RA4/T0CKI_6") (pintype "bidirectional"))
      (node (ref "JP15") (pin "5") (pinfunction "5_5") (pintype "passive"))
      (node (ref "R12") (pin "1") (pinfunction "1_1") (pintype "passive"))
    )
    (net (code "72") (name "Net-(IC3-RA5{slash}AN4)") (class "Default")
      (node (ref "IC3") (pin "7") (pinfunction "RA5/AN4_7") (pintype "bidirectional"))
      (node (ref "JP15") (pin "6") (pinfunction "6_6") (pintype "passive"))
    )
    (net (code "73") (name "Net-(IC3-RB1)") (class "Default")
      (node (ref "IC3") (pin "22") (pinfunction "RB1_22") (pintype "bidirectional"))
      (node (ref "JP18") (pin "7") (pinfunction "7_7") (pintype "passive"))
    )
    (net (code "74") (name "Net-(IC3-RB2)") (class "Default")
      (node (ref "IC3") (pin "23") (pinfunction "RB2_23") (pintype "bidirectional"))
      (node (ref "JP18") (pin "6") (pinfunction "6_6") (pintype "passive"))
    )
    (net (code "75") (name "Net-(IC3-RB4)") (class "Default")
      (node (ref "IC3") (pin "25") (pinfunction "RB4_25") (pintype "bidirectional"))
      (node (ref "JP18") (pin "4") (pinfunction "4_4") (pintype "passive"))
    )
    (net (code "76") (name "Net-(IC3-RB5)") (class "Default")
      (node (ref "IC3") (pin "26") (pinfunction "RB5_26") (pintype "bidirectional"))
      (node (ref "JP18") (pin "3") (pinfunction "3_3") (pintype "passive"))
    )
    (net (code "77") (name "Net-(IC3-RC0{slash}T1OSO)") (class "Default")
      (node (ref "IC3") (pin "11") (pinfunction "RC0/T1OSO_11") (pintype "bidirectional"))
      (node (ref "JP15") (pin "7") (pinfunction "7_7") (pintype "passive"))
    )
    (net (code "78") (name "Net-(IC3-RC1{slash}T1OSI)") (class "Default")
      (node (ref "IC3") (pin "12") (pinfunction "RC1/T1OSI_12") (pintype "bidirectional"))
      (node (ref "JP15") (pin "8") (pinfunction "8_8") (pintype "passive"))
    )
    (net (code "79") (name "Net-(IC3-RC2{slash}CCP1)") (class "Default")
      (node (ref "IC3") (pin "13") (pinfunction "RC2/CCP1_13") (pintype "bidirectional"))
      (node (ref "JP15") (pin "9") (pinfunction "9_9") (pintype "passive"))
    )
    (net (code "80") (name "Net-(IC3-RC6)") (class "Default")
      (node (ref "IC3") (pin "17") (pinfunction "RC6_17") (pintype "bidirectional"))
      (node (ref "JP18") (pin "10") (pinfunction "10_10") (pintype "passive"))
    )
    (net (code "81") (name "Net-(IC3-RC7)") (class "Default")
      (node (ref "IC3") (pin "18") (pinfunction "RC7_18") (pintype "bidirectional"))
      (node (ref "JP18") (pin "9") (pinfunction "9_9") (pintype "passive"))
    )
    (net (code "82") (name "Net-(IC3-SDO{slash}RC5)") (class "Default")
      (node (ref "IC3") (pin "16") (pinfunction "SDO/RC5_16") (pintype "bidirectional"))
      (node (ref "JP15") (pin "10") (pinfunction "10_10") (pintype "passive"))
    )
    (net (code "83") (name "Net-(IC4-REFIN)") (class "Default")
      (node (ref "IC4") (pin "6") (pinfunction "REFIN_6") (pintype "bidirectional"))
      (node (ref "IC5") (pin "8") (pinfunction "C_8") (pintype "passive"))
      (node (ref "R6") (pin "1") (pinfunction "1_1") (pintype "passive"))
    )
    (net (code "84") (name "Net-(IC4-VIN1)") (class "Default")
      (node (ref "IC4") (pin "7") (pinfunction "VIN1_7") (pintype "input"))
      (node (ref "JP12") (pin "1") (pinfunction "1_1") (pintype "passive"))
    )
    (net (code "85") (name "Net-(IC4-VIN2)") (class "Default")
      (node (ref "IC4") (pin "14") (pinfunction "VIN2_14") (pintype "input"))
      (node (ref "JP12") (pin "2") (pinfunction "2_2") (pintype "passive"))
    )
    (net (code "86") (name "Net-(IC4-VIN3)") (class "Default")
      (node (ref "IC4") (pin "8") (pinfunction "VIN3_8") (pintype "bidirectional"))
      (node (ref "JP12") (pin "3") (pinfunction "3_3") (pintype "passive"))
    )
    (net (code "87") (name "Net-(IC4-VIN4)") (class "Default")
      (node (ref "IC4") (pin "13") (pinfunction "VIN4_13") (pintype "bidirectional"))
      (node (ref "JP12") (pin "4") (pinfunction "4_4") (pintype "passive"))
    )
    (net (code "88") (name "Net-(IC4-VIN5)") (class "Default")
      (node (ref "IC4") (pin "9") (pinfunction "VIN5_9") (pintype "bidirectional"))
      (node (ref "JP12") (pin "5") (pinfunction "5_5") (pintype "passive"))
    )
    (net (code "89") (name "Net-(IC4-VIN6)") (class "Default")
      (node (ref "IC4") (pin "12") (pinfunction "VIN6_12") (pintype "bidirectional"))
      (node (ref "JP12") (pin "6") (pinfunction "6_6") (pintype "passive"))
    )
    (net (code "90") (name "Net-(IC4-VIN7)") (class "Default")
      (node (ref "IC4") (pin "10") (pinfunction "VIN7_10") (pintype "bidirectional"))
      (node (ref "JP12") (pin "7") (pinfunction "7_7") (pintype "passive"))
    )
    (net (code "91") (name "Net-(IC4-VIN8)") (class "Default")
      (node (ref "IC4") (pin "11") (pinfunction "VIN8_11") (pintype "bidirectional"))
      (node (ref "JP12") (pin "8") (pinfunction "8_8") (pintype "passive"))
    )
    (net (code "92") (name "Net-(IC4-~{CONVST})") (class "Default")
      (node (ref "IC4") (pin "16") (pinfunction "~{CONVST}_16") (pintype "input"))
      (node (ref "R5") (pin "2") (pinfunction "2_2") (pintype "passive"))
    )
    (net (code "93") (name "Net-(IC7-IN)") (class "Default")
      (node (ref "C11") (pin "1") (pinfunction "1_1") (pintype "passive"))
      (node (ref "F1") (pin "1") (pinfunction "1_1") (pintype "passive"))
      (node (ref "IC7") (pin "1") (pinfunction "IN_1") (pintype "passive"))
    )
    (net (code "94") (name "Net-(IC7-OUT)") (class "Default")
      (node (ref "C12") (pin "+") (pinfunction "+_+") (pintype "passive"))
      (node (ref "IC7") (pin "2") (pinfunction "OUT_2") (pintype "power_in"))
      (node (ref "JP16") (pin "1") (pinfunction "1_1") (pintype "passive"))
      (node (ref "JP16") (pin "10") (pinfunction "10_10") (pintype "passive"))
      (node (ref "JP16") (pin "2") (pinfunction "2_2") (pintype "passive"))
      (node (ref "JP16") (pin "3") (pinfunction "3_3") (pintype "passive"))
      (node (ref "JP16") (pin "4") (pinfunction "4_4") (pintype "passive"))
      (node (ref "JP16") (pin "5") (pinfunction "5_5") (pintype "passive"))
      (node (ref "JP16") (pin "6") (pinfunction "6_6") (pintype "passive"))
      (node (ref "JP16") (pin "7") (pinfunction "7_7") (pintype "passive"))
      (node (ref "JP16") (pin "8") (pinfunction "8_8") (pintype "passive"))
      (node (ref "JP16") (pin "9") (pinfunction "9_9") (pintype "passive"))
      (node (ref "JP19") (pin "1") (pinfunction "1_1") (pintype "passive"))
      (node (ref "JP19") (pin "10") (pinfunction "10_10") (pintype "passive"))
      (node (ref "JP19") (pin "2") (pinfunction "2_2") (pintype "passive"))
      (node (ref "JP19") (pin "3") (pinfunction "3_3") (pintype "passive"))
      (node (ref "JP19") (pin "4") (pinfunction "4_4") (pintype "passive"))
      (node (ref "JP19") (pin "5") (pinfunction "5_5") (pintype "passive"))
      (node (ref "JP19") (pin "6") (pinfunction "6_6") (pintype "passive"))
      (node (ref "JP19") (pin "7") (pinfunction "7_7") (pintype "passive"))
      (node (ref "JP19") (pin "8") (pinfunction "8_8") (pintype "passive"))
      (node (ref "JP19") (pin "9") (pinfunction "9_9") (pintype "passive"))
    )
    (net (code "95") (name "Net-(LED1-PadC)") (class "Default")
      (node (ref "LED1") (pin "C") (pinfunction "C_C") (pintype "passive"))
      (node (ref "R13") (pin "2") (pinfunction "2_2") (pintype "passive"))
    )
    (net (code "96") (name "unconnected-(IC1-INTB-Pad19)") (class "Default")
      (node (ref "IC1") (pin "19") (pinfunction "INTB_19") (pintype "output"))
    )
    (net (code "97") (name "unconnected-(IC4-ALERT-Pad17)") (class "Default")
      (node (ref "IC4") (pin "17") (pinfunction "ALERT_17") (pintype "output"))
    )
    (net (code "98") (name "unconnected-(IC5-ADJ-Pad5)") (class "Default")
      (node (ref "IC5") (pin "5") (pinfunction "ADJ_5") (pintype "input"))
    )
    (net (code "99") (name "unconnected-(SD-DAT1|---Pad8)") (class "Default")
      (node (ref "SD") (pin "8") (pinfunction "DAT1|--_8") (pintype "bidirectional"))
    )
    (net (code "100") (name "unconnected-(SD-DAT2|---Pad9)") (class "Default")
      (node (ref "SD") (pin "9") (pinfunction "DAT2|--_9") (pintype "bidirectional"))
    )
    (net (code "101") (name "unconnected-(SRV1-PWR-Pad1)") (class "Default")
      (node (ref "SRV1-PWR") (pin "1") (pinfunction "1_1") (pintype "passive"))
    )
    (net (code "102") (name "unconnected-(SRV1-PWR-Pad2)") (class "Default")
      (node (ref "SRV1-PWR") (pin "2") (pinfunction "2_2") (pintype "passive"))
    )
  )
)
